# Integrators.net
KiCad netlist of a schematic drawn in Altium Designer
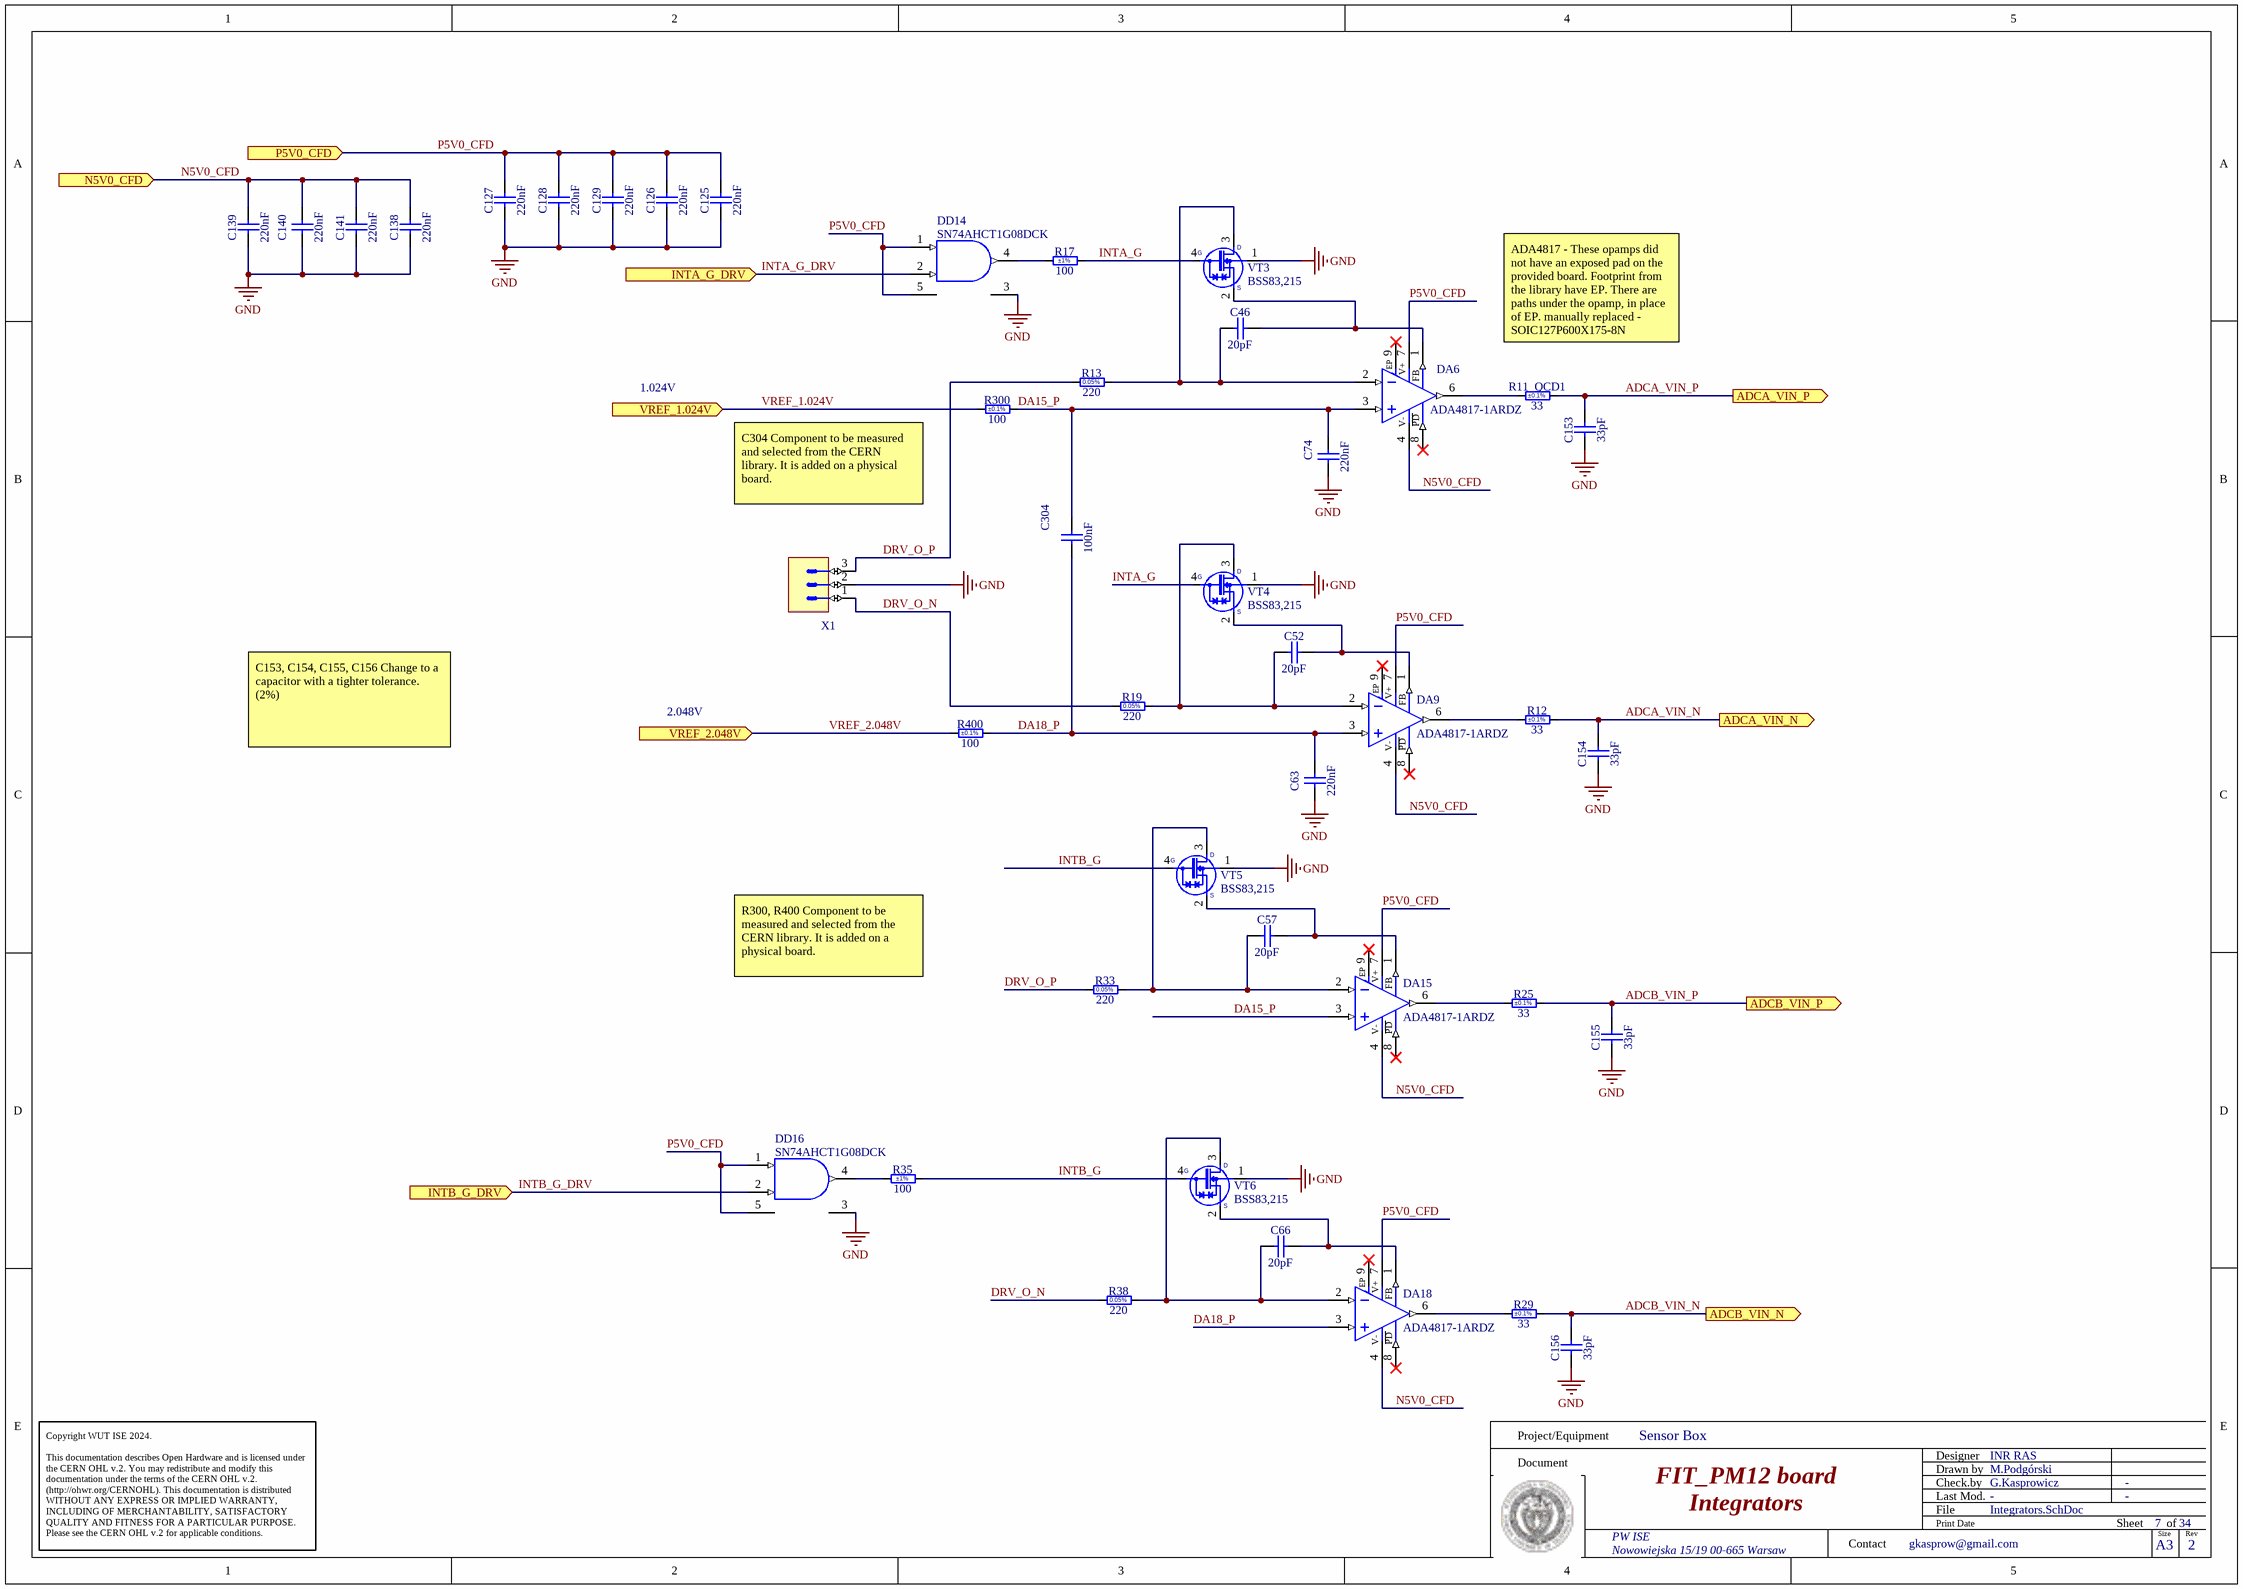
[diagram p0: Integrators.SchDoc]

(export (version "E")
  (design (tool "Eeschema 10.0.6"))
  (components
    (comp (ref "C46")
      (value "20pF")
      (footprint "CAPC2012X135N")
      (description "Non-polarised capacitor")
      (fields
        (field (name "PART NUMBER") "CC0805_20PF_50V_2%_C0G")
        (field (name "VOLTAGE") "50V")
        (field (name "AUTHOR") "CERN DEM HF")
      )
      (libsource (lib "Capacitors") (part "Capacitor - non polarized"))
    )
    (comp (ref "C52")
      (value "20pF")
      (footprint "CAPC2012X135N")
      (description "Non-polarised capacitor")
      (fields
        (field (name "PART NUMBER") "CC0805_20PF_50V_2%_C0G")
        (field (name "VOLTAGE") "50V")
        (field (name "AUTHOR") "CERN DEM HF")
      )
      (libsource (lib "Capacitors") (part "Capacitor - non polarized"))
    )
    (comp (ref "C57")
      (value "20pF")
      (footprint "CAPC2012X135N")
      (description "Non-polarised capacitor")
      (fields
        (field (name "PART NUMBER") "CC0805_20PF_50V_2%_C0G")
        (field (name "VOLTAGE") "50V")
        (field (name "AUTHOR") "CERN DEM HF")
      )
      (libsource (lib "Capacitors") (part "Capacitor - non polarized"))
    )
    (comp (ref "C63")
      (value "220nF")
      (footprint "CAPC2012X135N")
      (description "Non-polarised capacitor")
      (fields
        (field (name "PART NUMBER") "CC0805_220NF_50V_10%_X7R")
        (field (name "VOLTAGE") "50V")
        (field (name "AUTHOR") "CERN DEM JLC")
      )
      (libsource (lib "Capacitors") (part "Capacitor - non polarized"))
    )
    (comp (ref "C66")
      (value "20pF")
      (footprint "CAPC2012X135N")
      (description "Non-polarised capacitor")
      (fields
        (field (name "PART NUMBER") "CC0805_20PF_50V_2%_C0G")
        (field (name "VOLTAGE") "50V")
        (field (name "AUTHOR") "CERN DEM HF")
      )
      (libsource (lib "Capacitors") (part "Capacitor - non polarized"))
    )
    (comp (ref "C74")
      (value "220nF")
      (footprint "CAPC2012X135N")
      (description "Non-polarised capacitor")
      (fields
        (field (name "PART NUMBER") "CC0805_220NF_50V_10%_X7R")
        (field (name "VOLTAGE") "50V")
        (field (name "AUTHOR") "CERN DEM JLC")
      )
      (libsource (lib "Capacitors") (part "Capacitor - non polarized"))
    )
    (comp (ref "C125")
      (value "220nF")
      (footprint "CAPC2012X135N")
      (description "Non-polarised capacitor")
      (fields
        (field (name "PART NUMBER") "CC0805_220NF_50V_10%_X7R")
        (field (name "VOLTAGE") "50V")
        (field (name "AUTHOR") "CERN DEM JLC")
      )
      (libsource (lib "Capacitors") (part "Capacitor - non polarized"))
    )
    (comp (ref "C126")
      (value "220nF")
      (footprint "CAPC2012X135N")
      (description "Non-polarised capacitor")
      (fields
        (field (name "PART NUMBER") "CC0805_220NF_50V_10%_X7R")
        (field (name "VOLTAGE") "50V")
        (field (name "AUTHOR") "CERN DEM JLC")
      )
      (libsource (lib "Capacitors") (part "Capacitor - non polarized"))
    )
    (comp (ref "C127")
      (value "220nF")
      (footprint "CAPC2012X135N")
      (description "Non-polarised capacitor")
      (fields
        (field (name "PART NUMBER") "CC0805_220NF_50V_10%_X7R")
        (field (name "VOLTAGE") "50V")
        (field (name "AUTHOR") "CERN DEM JLC")
      )
      (libsource (lib "Capacitors") (part "Capacitor - non polarized"))
    )
    (comp (ref "C128")
      (value "220nF")
      (footprint "CAPC2012X135N")
      (description "Non-polarised capacitor")
      (fields
        (field (name "PART NUMBER") "CC0805_220NF_50V_10%_X7R")
        (field (name "VOLTAGE") "50V")
        (field (name "AUTHOR") "CERN DEM JLC")
      )
      (libsource (lib "Capacitors") (part "Capacitor - non polarized"))
    )
    (comp (ref "C129")
      (value "220nF")
      (footprint "CAPC2012X135N")
      (description "Non-polarised capacitor")
      (fields
        (field (name "PART NUMBER") "CC0805_220NF_50V_10%_X7R")
        (field (name "VOLTAGE") "50V")
        (field (name "AUTHOR") "CERN DEM JLC")
      )
      (libsource (lib "Capacitors") (part "Capacitor - non polarized"))
    )
    (comp (ref "C138")
      (value "220nF")
      (footprint "CAPC2012X135N")
      (description "Non-polarised capacitor")
      (fields
        (field (name "PART NUMBER") "CC0805_220NF_50V_10%_X7R")
        (field (name "VOLTAGE") "50V")
        (field (name "AUTHOR") "CERN DEM JLC")
      )
      (libsource (lib "Capacitors") (part "Capacitor - non polarized"))
    )
    (comp (ref "C139")
      (value "220nF")
      (footprint "CAPC2012X135N")
      (description "Non-polarised capacitor")
      (fields
        (field (name "PART NUMBER") "CC0805_220NF_50V_10%_X7R")
        (field (name "VOLTAGE") "50V")
        (field (name "AUTHOR") "CERN DEM JLC")
      )
      (libsource (lib "Capacitors") (part "Capacitor - non polarized"))
    )
    (comp (ref "C140")
      (value "220nF")
      (footprint "CAPC2012X135N")
      (description "Non-polarised capacitor")
      (fields
        (field (name "PART NUMBER") "CC0805_220NF_50V_10%_X7R")
        (field (name "VOLTAGE") "50V")
        (field (name "AUTHOR") "CERN DEM JLC")
      )
      (libsource (lib "Capacitors") (part "Capacitor - non polarized"))
    )
    (comp (ref "C141")
      (value "220nF")
      (footprint "CAPC2012X135N")
      (description "Non-polarised capacitor")
      (fields
        (field (name "PART NUMBER") "CC0805_220NF_50V_10%_X7R")
        (field (name "VOLTAGE") "50V")
        (field (name "AUTHOR") "CERN DEM JLC")
      )
      (libsource (lib "Capacitors") (part "Capacitor - non polarized"))
    )
    (comp (ref "C153")
      (value "33pF")
      (footprint "CAPC1608X87N")
      (description "Non-polarised capacitor")
      (fields
        (field (name "PART NUMBER") "CC0603_33PF_50V_5%_NP0")
        (field (name "VOLTAGE") "50V")
        (field (name "AUTHOR") "CERN DEM JLC")
      )
      (libsource (lib "Capacitors") (part "Capacitor - non polarized"))
    )
    (comp (ref "C154")
      (value "33pF")
      (footprint "CAPC1608X87N")
      (description "Non-polarised capacitor")
      (fields
        (field (name "PART NUMBER") "CC0603_33PF_50V_5%_NP0")
        (field (name "VOLTAGE") "50V")
        (field (name "AUTHOR") "CERN DEM JLC")
      )
      (libsource (lib "Capacitors") (part "Capacitor - non polarized"))
    )
    (comp (ref "C155")
      (value "33pF")
      (footprint "CAPC1608X87N")
      (description "Non-polarised capacitor")
      (fields
        (field (name "PART NUMBER") "CC0603_33PF_50V_5%_NP0")
        (field (name "VOLTAGE") "50V")
        (field (name "AUTHOR") "CERN DEM JLC")
      )
      (libsource (lib "Capacitors") (part "Capacitor - non polarized"))
    )
    (comp (ref "C156")
      (value "33pF")
      (footprint "CAPC1608X87N")
      (description "Non-polarised capacitor")
      (fields
        (field (name "PART NUMBER") "CC0603_33PF_50V_5%_NP0")
        (field (name "VOLTAGE") "50V")
        (field (name "AUTHOR") "CERN DEM JLC")
      )
      (libsource (lib "Capacitors") (part "Capacitor - non polarized"))
    )
    (comp (ref "C304")
      (value "100nF")
      (footprint "CAPC2012X88N")
      (description "Non-polarised capacitor")
      (fields
        (field (name "PART NUMBER") "CC0805_100NF_50V_1%_NP0")
        (field (name "VOLTAGE") "50V")
        (field (name "AUTHOR") "CERN DEM HF")
      )
      (libsource (lib "Capacitors") (part "Capacitor - non polarized"))
    )
    (comp (ref "DA6")
      (value "ADA4817-1ARDZ")
      (footprint "SOIC127P600X175-8N")
      (description "Low Noise, 1GHz FastFEET Operational Amplifier")
      (fields
        (field (name "MANUFACTURER") "ANALOG DEVICES")
        (field (name "MANUFACTURER PART NUMBER") "ADA4817-1ARD")
        (field (name "AUTHOR") "CERN DEM JLC")
      )
      (libsource (lib "ICs And Semiconductors") (part "ADA4817-1ARDZ"))
    )
    (comp (ref "DA9")
      (value "ADA4817-1ARDZ")
      (footprint "SOIC127P600X175-8N")
      (description "Low Noise, 1GHz FastFEET Operational Amplifier")
      (fields
        (field (name "MANUFACTURER") "ANALOG DEVICES")
        (field (name "MANUFACTURER PART NUMBER") "ADA4817-1ARD")
        (field (name "AUTHOR") "CERN DEM JLC")
      )
      (libsource (lib "ICs And Semiconductors") (part "ADA4817-1ARDZ"))
    )
    (comp (ref "DA15")
      (value "ADA4817-1ARDZ")
      (footprint "SOIC127P600X175-8N")
      (description "Low Noise, 1GHz FastFEET Operational Amplifier")
      (fields
        (field (name "MANUFACTURER") "ANALOG DEVICES")
        (field (name "MANUFACTURER PART NUMBER") "ADA4817-1ARD")
        (field (name "AUTHOR") "CERN DEM JLC")
      )
      (libsource (lib "ICs And Semiconductors") (part "ADA4817-1ARDZ"))
    )
    (comp (ref "DA18")
      (value "ADA4817-1ARDZ")
      (footprint "SOIC127P600X175-8N")
      (description "Low Noise, 1GHz FastFEET Operational Amplifier")
      (fields
        (field (name "MANUFACTURER") "ANALOG DEVICES")
        (field (name "MANUFACTURER PART NUMBER") "ADA4817-1ARD")
        (field (name "AUTHOR") "CERN DEM JLC")
      )
      (libsource (lib "ICs And Semiconductors") (part "ADA4817-1ARDZ"))
    )
    (comp (ref "DD14")
      (value "SN74AHCT1G08DCK")
      (footprint "SOT65P210X110-5N")
      (description "Single 2-Input AND Gate")
      (fields (field (name "MANUFACTURER") "TEXAS INSTRUMENTS") (field (name "AUTHOR") "CERN DEM HF"))
      (libsource (lib "ICs And Semiconductors") (part "741G08"))
    )
    (comp (ref "DD16")
      (value "SN74AHCT1G08DCK")
      (footprint "SOT65P210X110-5N")
      (description "Single 2-Input AND Gate")
      (fields (field (name "MANUFACTURER") "TEXAS INSTRUMENTS") (field (name "AUTHOR") "CERN DEM HF"))
      (libsource (lib "ICs And Semiconductors") (part "741G08"))
    )
    (comp (ref "R11_QCD1")
      (value "33")
      (footprint "RESC1608X64N")
      (description "Resistor - 0.1%")
      (fields
        (field (name "TOLERANCE") "±0.1%")
        (field (name "PART NUMBER") "R0603_33R_0.1%_0.1W_10PPM")
        (field (name "POWER") "0.1W")
        (field (name "AUTHOR") "CERN DEM HF")
      )
      (libsource (lib "Resistors") (part "Resistor - 0.1%"))
    )
    (comp (ref "R12")
      (value "33")
      (footprint "RESC1608X64N")
      (description "Resistor - 0.1%")
      (fields
        (field (name "TOLERANCE") "±0.1%")
        (field (name "PART NUMBER") "R0603_33R_0.1%_0.1W_10PPM")
        (field (name "POWER") "0.1W")
        (field (name "AUTHOR") "CERN DEM HF")
      )
      (libsource (lib "Resistors") (part "Resistor - 0.1%"))
    )
    (comp (ref "R13")
      (value "220")
      (footprint "RESC2012X60N")
      (description "Resistor - 0.05%")
      (fields
        (field (name "PART NUMBER") "R0805_220R_0.05%_0.125W_10PPM")
        (field (name "POWER") "0.125W")
        (field (name "AUTHOR") "CERN DEM HF")
      )
      (libsource (lib "Resistors") (part "Resistor - 0.05%"))
    )
    (comp (ref "R17")
      (value "100")
      (footprint "RESC1608X55N")
      (description "Resistor - 1%")
      (fields
        (field (name "TOLERANCE") "±1%")
        (field (name "PART NUMBER") "R0603_100R_1%_0.1W_100PPM")
        (field (name "POWER") "0.1W")
        (field (name "AUTHOR") "CERN DEM JLC")
      )
      (libsource (lib "Resistors") (part "Resistor - 1%"))
    )
    (comp (ref "R19")
      (value "220")
      (footprint "RESC2012X60N")
      (description "Resistor - 0.05%")
      (fields
        (field (name "PART NUMBER") "R0805_220R_0.05%_0.125W_10PPM")
        (field (name "POWER") "0.125W")
        (field (name "AUTHOR") "CERN DEM HF")
      )
      (libsource (lib "Resistors") (part "Resistor - 0.05%"))
    )
    (comp (ref "R25")
      (value "33")
      (footprint "RESC1608X64N")
      (description "Resistor - 0.1%")
      (fields
        (field (name "TOLERANCE") "±0.1%")
        (field (name "PART NUMBER") "R0603_33R_0.1%_0.1W_10PPM")
        (field (name "POWER") "0.1W")
        (field (name "AUTHOR") "CERN DEM HF")
      )
      (libsource (lib "Resistors") (part "Resistor - 0.1%"))
    )
    (comp (ref "R29")
      (value "33")
      (footprint "RESC1608X64N")
      (description "Resistor - 0.1%")
      (fields
        (field (name "TOLERANCE") "±0.1%")
        (field (name "PART NUMBER") "R0603_33R_0.1%_0.1W_10PPM")
        (field (name "POWER") "0.1W")
        (field (name "AUTHOR") "CERN DEM HF")
      )
      (libsource (lib "Resistors") (part "Resistor - 0.1%"))
    )
    (comp (ref "R33")
      (value "220")
      (footprint "RESC2012X60N")
      (description "Resistor - 0.05%")
      (fields
        (field (name "PART NUMBER") "R0805_220R_0.05%_0.125W_10PPM")
        (field (name "POWER") "0.125W")
        (field (name "AUTHOR") "CERN DEM HF")
      )
      (libsource (lib "Resistors") (part "Resistor - 0.05%"))
    )
    (comp (ref "R35")
      (value "100")
      (footprint "RESC1608X55N")
      (description "Resistor - 1%")
      (fields
        (field (name "TOLERANCE") "±1%")
        (field (name "PART NUMBER") "R0603_100R_1%_0.1W_100PPM")
        (field (name "POWER") "0.1W")
        (field (name "AUTHOR") "CERN DEM JLC")
      )
      (libsource (lib "Resistors") (part "Resistor - 1%"))
    )
    (comp (ref "R38")
      (value "220")
      (footprint "RESC2012X60N")
      (description "Resistor - 0.05%")
      (fields
        (field (name "PART NUMBER") "R0805_220R_0.05%_0.125W_10PPM")
        (field (name "POWER") "0.125W")
        (field (name "AUTHOR") "CERN DEM HF")
      )
      (libsource (lib "Resistors") (part "Resistor - 0.05%"))
    )
    (comp (ref "R300")
      (value "100")
      (footprint "RES_VISHAY_FCHP0402")
      (description "Resistor - 0.1%")
      (fields
        (field (name "TOLERANCE") "±0.1%")
        (field (name "PART NUMBER") "R0402_100R_0.1%_1W_25PPM_VISHAY_FCHP0402E1000BS")
        (field (name "POWER") "1W")
        (field (name "AUTHOR") "CERN DEM HF")
      )
      (libsource (lib "Resistors") (part "Resistor - 0.1%"))
    )
    (comp (ref "R400")
      (value "100")
      (footprint "RES_VISHAY_FCHP0402")
      (description "Resistor - 0.1%")
      (fields
        (field (name "TOLERANCE") "±0.1%")
        (field (name "PART NUMBER") "R0402_100R_0.1%_1W_25PPM_VISHAY_FCHP0402E1000BS")
        (field (name "POWER") "1W")
        (field (name "AUTHOR") "CERN DEM HF")
      )
      (libsource (lib "Resistors") (part "Resistor - 0.1%"))
    )
    (comp (ref "VT3")
      (value "BSS83,215")
      (footprint "SOT143N")
      (description "10V, 50 mA N-Channel Enhancement Switching Transistor")
      (fields (field (name "MANUFACTURER") "NXP SEMICONDUCTORS") (field (name "AUTHOR") "CERN DEM JLC"))
      (libsource (lib "ICs And Semiconductors") (part "BSS83"))
    )
    (comp (ref "VT4")
      (value "BSS83,215")
      (footprint "SOT143N")
      (description "10V, 50 mA N-Channel Enhancement Switching Transistor")
      (fields (field (name "MANUFACTURER") "NXP SEMICONDUCTORS") (field (name "AUTHOR") "CERN DEM JLC"))
      (libsource (lib "ICs And Semiconductors") (part "BSS83"))
    )
    (comp (ref "VT5")
      (value "BSS83,215")
      (footprint "SOT143N")
      (description "10V, 50 mA N-Channel Enhancement Switching Transistor")
      (fields (field (name "MANUFACTURER") "NXP SEMICONDUCTORS") (field (name "AUTHOR") "CERN DEM JLC"))
      (libsource (lib "ICs And Semiconductors") (part "BSS83"))
    )
    (comp (ref "VT6")
      (value "BSS83,215")
      (footprint "SOT143N")
      (description "10V, 50 mA N-Channel Enhancement Switching Transistor")
      (fields (field (name "MANUFACTURER") "NXP SEMICONDUCTORS") (field (name "AUTHOR") "CERN DEM JLC"))
      (libsource (lib "ICs And Semiconductors") (part "BSS83"))
    )
    (comp (ref "X1")
      (value "Header 3")
      (footprint "SAMTEC_DW-03-09-L-S-470")
      (description "Connector 3 Male")
      (fields
        (field (name "PART NUMBER") "SAMTEC_DW-03-09-L-S-470")
        (field (name "MANUFACTURER") "SAMTEC")
        (field (name "AUTHOR") "CERN DEM HF")
      )
      (libsource (lib "Connectors") (part "Connector 3 Male"))
    )
  )
  (nets
    (net (code "1") (name "/ADCA_VIN_N") (class "Default")
      (node (ref "C154") (pin "2") (pinfunction "2_2") (pintype "passive"))
      (node (ref "R12") (pin "2") (pinfunction "2_2") (pintype "passive"))
    )
    (net (code "2") (name "/ADCA_VIN_P") (class "Default")
      (node (ref "C153") (pin "2") (pinfunction "2_2") (pintype "passive"))
      (node (ref "R11_QCD1") (pin "2") (pinfunction "2_2") (pintype "passive"))
    )
    (net (code "3") (name "/ADCB_VIN_N") (class "Default")
      (node (ref "C156") (pin "2") (pinfunction "2_2") (pintype "passive"))
      (node (ref "R29") (pin "2") (pinfunction "2_2") (pintype "passive"))
    )
    (net (code "4") (name "/ADCB_VIN_P") (class "Default")
      (node (ref "C155") (pin "2") (pinfunction "2_2") (pintype "passive"))
      (node (ref "R25") (pin "2") (pinfunction "2_2") (pintype "passive"))
    )
    (net (code "5") (name "/DA15_P") (class "Default")
      (node (ref "C304") (pin "2") (pinfunction "2_2") (pintype "passive"))
      (node (ref "C74") (pin "2") (pinfunction "2_2") (pintype "passive"))
      (node (ref "DA15") (pin "3") (pinfunction "IN+_3") (pintype "input"))
      (node (ref "DA6") (pin "3") (pinfunction "IN+_3") (pintype "input"))
      (node (ref "R300") (pin "1") (pinfunction "1_1") (pintype "passive"))
    )
    (net (code "6") (name "/DA18_P") (class "Default")
      (node (ref "C304") (pin "1") (pinfunction "1_1") (pintype "passive"))
      (node (ref "C63") (pin "2") (pinfunction "2_2") (pintype "passive"))
      (node (ref "DA18") (pin "3") (pinfunction "IN+_3") (pintype "input"))
      (node (ref "DA9") (pin "3") (pinfunction "IN+_3") (pintype "input"))
      (node (ref "R400") (pin "1") (pinfunction "1_1") (pintype "passive"))
    )
    (net (code "7") (name "/DRV_O_N") (class "Default")
      (node (ref "R19") (pin "1") (pinfunction "1_1") (pintype "passive"))
      (node (ref "R38") (pin "1") (pinfunction "1_1") (pintype "passive"))
      (node (ref "X1") (pin "1") (pinfunction "1_1") (pintype "bidirectional"))
    )
    (net (code "8") (name "/DRV_O_P") (class "Default")
      (node (ref "R13") (pin "1") (pinfunction "1_1") (pintype "passive"))
      (node (ref "R33") (pin "1") (pinfunction "1_1") (pintype "passive"))
      (node (ref "X1") (pin "3") (pinfunction "3_3") (pintype "bidirectional"))
    )
    (net (code "9") (name "/INTA_G") (class "Default")
      (node (ref "R17") (pin "2") (pinfunction "2_2") (pintype "passive"))
      (node (ref "VT3") (pin "4") (pinfunction "G_4") (pintype "passive"))
      (node (ref "VT4") (pin "4") (pinfunction "G_4") (pintype "passive"))
    )
    (net (code "10") (name "/INTA_G_DRV") (class "Default")
      (node (ref "DD14") (pin "2") (pinfunction "A_2") (pintype "input"))
    )
    (net (code "11") (name "/INTB_G") (class "Default")
      (node (ref "R35") (pin "2") (pinfunction "2_2") (pintype "passive"))
      (node (ref "VT5") (pin "4") (pinfunction "G_4") (pintype "passive"))
      (node (ref "VT6") (pin "4") (pinfunction "G_4") (pintype "passive"))
    )
    (net (code "12") (name "/INTB_G_DRV") (class "Default")
      (node (ref "DD16") (pin "2") (pinfunction "A_2") (pintype "input"))
    )
    (net (code "13") (name "/N5V0_CFD") (class "Default")
      (node (ref "C138") (pin "2") (pinfunction "2_2") (pintype "passive"))
      (node (ref "C139") (pin "2") (pinfunction "2_2") (pintype "passive"))
      (node (ref "C140") (pin "2") (pinfunction "2_2") (pintype "passive"))
      (node (ref "C141") (pin "2") (pinfunction "2_2") (pintype "passive"))
      (node (ref "DA15") (pin "4") (pinfunction "-Vs_4") (pintype "power_in"))
      (node (ref "DA18") (pin "4") (pinfunction "-Vs_4") (pintype "power_in"))
      (node (ref "DA6") (pin "4") (pinfunction "-Vs_4") (pintype "power_in"))
      (node (ref "DA9") (pin "4") (pinfunction "-Vs_4") (pintype "power_in"))
    )
    (net (code "14") (name "/P5V0_CFD") (class "Default")
      (node (ref "C125") (pin "2") (pinfunction "2_2") (pintype "passive"))
      (node (ref "C126") (pin "2") (pinfunction "2_2") (pintype "passive"))
      (node (ref "C127") (pin "2") (pinfunction "2_2") (pintype "passive"))
      (node (ref "C128") (pin "2") (pinfunction "2_2") (pintype "passive"))
      (node (ref "C129") (pin "2") (pinfunction "2_2") (pintype "passive"))
      (node (ref "DA15") (pin "7") (pinfunction "+Vs_7") (pintype "power_in"))
      (node (ref "DA18") (pin "7") (pinfunction "+Vs_7") (pintype "power_in"))
      (node (ref "DA6") (pin "7") (pinfunction "+Vs_7") (pintype "power_in"))
      (node (ref "DA9") (pin "7") (pinfunction "+Vs_7") (pintype "power_in"))
      (node (ref "DD14") (pin "1") (pinfunction "B_1") (pintype "input"))
      (node (ref "DD14") (pin "5") (pinfunction "VCC_5") (pintype "power_in"))
      (node (ref "DD16") (pin "1") (pinfunction "B_1") (pintype "input"))
      (node (ref "DD16") (pin "5") (pinfunction "VCC_5") (pintype "power_in"))
    )
    (net (code "15") (name "/VREF_1.024V") (class "Default")
      (node (ref "R300") (pin "2") (pinfunction "2_2") (pintype "passive"))
    )
    (net (code "16") (name "/VREF_2.048V") (class "Default")
      (node (ref "R400") (pin "2") (pinfunction "2_2") (pintype "passive"))
    )
    (net (code "17") (name "GND") (class "Default")
      (node (ref "C125") (pin "1") (pinfunction "1_1") (pintype "passive"))
      (node (ref "C126") (pin "1") (pinfunction "1_1") (pintype "passive"))
      (node (ref "C127") (pin "1") (pinfunction "1_1") (pintype "passive"))
      (node (ref "C128") (pin "1") (pinfunction "1_1") (pintype "passive"))
      (node (ref "C129") (pin "1") (pinfunction "1_1") (pintype "passive"))
      (node (ref "C138") (pin "1") (pinfunction "1_1") (pintype "passive"))
      (node (ref "C139") (pin "1") (pinfunction "1_1") (pintype "passive"))
      (node (ref "C140") (pin "1") (pinfunction "1_1") (pintype "passive"))
      (node (ref "C141") (pin "1") (pinfunction "1_1") (pintype "passive"))
      (node (ref "C153") (pin "1") (pinfunction "1_1") (pintype "passive"))
      (node (ref "C154") (pin "1") (pinfunction "1_1") (pintype "passive"))
      (node (ref "C155") (pin "1") (pinfunction "1_1") (pintype "passive"))
      (node (ref "C156") (pin "1") (pinfunction "1_1") (pintype "passive"))
      (node (ref "C63") (pin "1") (pinfunction "1_1") (pintype "passive"))
      (node (ref "C74") (pin "1") (pinfunction "1_1") (pintype "passive"))
      (node (ref "DD14") (pin "3") (pinfunction "GND_3") (pintype "power_in"))
      (node (ref "DD16") (pin "3") (pinfunction "GND_3") (pintype "power_in"))
      (node (ref "VT3") (pin "1") (pinfunction "SUB_1") (pintype "passive"))
      (node (ref "VT4") (pin "1") (pinfunction "SUB_1") (pintype "passive"))
      (node (ref "VT5") (pin "1") (pinfunction "SUB_1") (pintype "passive"))
      (node (ref "VT6") (pin "1") (pinfunction "SUB_1") (pintype "passive"))
      (node (ref "X1") (pin "2") (pinfunction "2_2") (pintype "bidirectional"))
    )
    (net (code "18") (name "Net-(DA6-FB)") (class "Default")
      (node (ref "C46") (pin "2") (pinfunction "2_2") (pintype "passive"))
      (node (ref "DA6") (pin "1") (pinfunction "FB_1") (pintype "output"))
      (node (ref "VT3") (pin "2") (pinfunction "S_2") (pintype "passive"))
    )
    (net (code "19") (name "Net-(DA6-IN-)") (class "Default")
      (node (ref "C46") (pin "1") (pinfunction "1_1") (pintype "passive"))
      (node (ref "DA6") (pin "2") (pinfunction "IN-_2") (pintype "input"))
      (node (ref "R13") (pin "2") (pinfunction "2_2") (pintype "passive"))
      (node (ref "VT3") (pin "3") (pinfunction "D_3") (pintype "passive"))
    )
    (net (code "20") (name "Net-(DA6-OUT)") (class "Default")
      (node (ref "DA6") (pin "6") (pinfunction "OUT_6") (pintype "output"))
      (node (ref "R11_QCD1") (pin "1") (pinfunction "1_1") (pintype "passive"))
    )
    (net (code "21") (name "Net-(DA9-FB)") (class "Default")
      (node (ref "C52") (pin "2") (pinfunction "2_2") (pintype "passive"))
      (node (ref "DA9") (pin "1") (pinfunction "FB_1") (pintype "output"))
      (node (ref "VT4") (pin "2") (pinfunction "S_2") (pintype "passive"))
    )
    (net (code "22") (name "Net-(DA9-IN-)") (class "Default")
      (node (ref "C52") (pin "1") (pinfunction "1_1") (pintype "passive"))
      (node (ref "DA9") (pin "2") (pinfunction "IN-_2") (pintype "input"))
      (node (ref "R19") (pin "2") (pinfunction "2_2") (pintype "passive"))
      (node (ref "VT4") (pin "3") (pinfunction "D_3") (pintype "passive"))
    )
    (net (code "23") (name "Net-(DA9-OUT)") (class "Default")
      (node (ref "DA9") (pin "6") (pinfunction "OUT_6") (pintype "output"))
      (node (ref "R12") (pin "1") (pinfunction "1_1") (pintype "passive"))
    )
    (net (code "24") (name "Net-(DA15-FB)") (class "Default")
      (node (ref "C57") (pin "2") (pinfunction "2_2") (pintype "passive"))
      (node (ref "DA15") (pin "1") (pinfunction "FB_1") (pintype "output"))
      (node (ref "VT5") (pin "2") (pinfunction "S_2") (pintype "passive"))
    )
    (net (code "25") (name "Net-(DA15-IN-)") (class "Default")
      (node (ref "C57") (pin "1") (pinfunction "1_1") (pintype "passive"))
      (node (ref "DA15") (pin "2") (pinfunction "IN-_2") (pintype "input"))
      (node (ref "R33") (pin "2") (pinfunction "2_2") (pintype "passive"))
      (node (ref "VT5") (pin "3") (pinfunction "D_3") (pintype "passive"))
    )
    (net (code "26") (name "Net-(DA15-OUT)") (class "Default")
      (node (ref "DA15") (pin "6") (pinfunction "OUT_6") (pintype "output"))
      (node (ref "R25") (pin "1") (pinfunction "1_1") (pintype "passive"))
    )
    (net (code "27") (name "Net-(DA18-FB)") (class "Default")
      (node (ref "C66") (pin "2") (pinfunction "2_2") (pintype "passive"))
      (node (ref "DA18") (pin "1") (pinfunction "FB_1") (pintype "output"))
      (node (ref "VT6") (pin "2") (pinfunction "S_2") (pintype "passive"))
    )
    (net (code "28") (name "Net-(DA18-IN-)") (class "Default")
      (node (ref "C66") (pin "1") (pinfunction "1_1") (pintype "passive"))
      (node (ref "DA18") (pin "2") (pinfunction "IN-_2") (pintype "input"))
      (node (ref "R38") (pin "2") (pinfunction "2_2") (pintype "passive"))
      (node (ref "VT6") (pin "3") (pinfunction "D_3") (pintype "passive"))
    )
    (net (code "29") (name "Net-(DA18-OUT)") (class "Default")
      (node (ref "DA18") (pin "6") (pinfunction "OUT_6") (pintype "output"))
      (node (ref "R29") (pin "1") (pinfunction "1_1") (pintype "passive"))
    )
    (net (code "30") (name "Net-(DD14-Y)") (class "Default")
      (node (ref "DD14") (pin "4") (pinfunction "Y_4") (pintype "output"))
      (node (ref "R17") (pin "1") (pinfunction "1_1") (pintype "passive"))
    )
    (net (code "31") (name "Net-(DD16-Y)") (class "Default")
      (node (ref "DD16") (pin "4") (pinfunction "Y_4") (pintype "output"))
      (node (ref "R35") (pin "1") (pinfunction "1_1") (pintype "passive"))
    )
    (net (code "32") (name "unconnected-(DA6-EP-Pad9)") (class "Default")
      (node (ref "DA6") (pin "9") (pinfunction "EP_9") (pintype "power_in+no_connect"))
    )
    (net (code "33") (name "unconnected-(DA6-~{PD}-Pad8)") (class "Default")
      (node (ref "DA6") (pin "8") (pinfunction "~{PD}_8") (pintype "input+no_connect"))
    )
    (net (code "34") (name "unconnected-(DA9-EP-Pad9)") (class "Default")
      (node (ref "DA9") (pin "9") (pinfunction "EP_9") (pintype "power_in+no_connect"))
    )
    (net (code "35") (name "unconnected-(DA9-~{PD}-Pad8)") (class "Default")
      (node (ref "DA9") (pin "8") (pinfunction "~{PD}_8") (pintype "input+no_connect"))
    )
    (net (code "36") (name "unconnected-(DA15-EP-Pad9)") (class "Default")
      (node (ref "DA15") (pin "9") (pinfunction "EP_9") (pintype "power_in+no_connect"))
    )
    (net (code "37") (name "unconnected-(DA15-~{PD}-Pad8)") (class "Default")
      (node (ref "DA15") (pin "8") (pinfunction "~{PD}_8") (pintype "input+no_connect"))
    )
    (net (code "38") (name "unconnected-(DA18-EP-Pad9)") (class "Default")
      (node (ref "DA18") (pin "9") (pinfunction "EP_9") (pintype "power_in+no_connect"))
    )
    (net (code "39") (name "unconnected-(DA18-~{PD}-Pad8)") (class "Default")
      (node (ref "DA18") (pin "8") (pinfunction "~{PD}_8") (pintype "input+no_connect"))
    )
  )
)
